# ECsimple.net
KiCad netlist of a schematic drawn in EAGLE
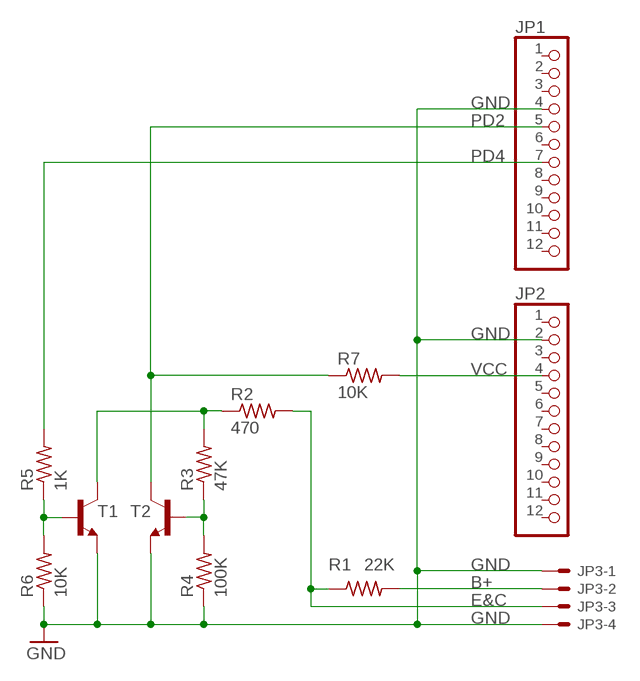
[diagram p0: schematic, sheet 1]

(export (version "E")
  (design (tool "Eeschema 10.0.6"))
  (components
    (comp (ref "JP1")
      (value "PINHD-1X12-CB")
      (footprint "eagle-import:1X12-CB")
      (libsource (lib "eagle-import") (part "PINHD-1X12-CB"))
    )
    (comp (ref "JP2")
      (value "PINHD-1X12-CB")
      (footprint "eagle-import:1X12-CB")
      (libsource (lib "eagle-import") (part "PINHD-1X12-CB"))
    )
    (comp (ref "JP3")
      (value "HDR_PLAIN_1X4")
      (footprint "eagle-import:HDR_1X4")
      (libsource (lib "eagle-import") (part "HDR_PLAIN_1X4"))
    )
    (comp (ref "R1")
      (value "22K")
      (footprint "eagle-import:0204_7")
      (libsource (lib "eagle-import") (part "R-US_0204/7"))
    )
    (comp (ref "R2")
      (value "470")
      (footprint "eagle-import:0204_7")
      (libsource (lib "eagle-import") (part "R-US_0204/7"))
    )
    (comp (ref "R3")
      (value "47K")
      (footprint "eagle-import:0204_7")
      (libsource (lib "eagle-import") (part "R-US_0204/7"))
    )
    (comp (ref "R4")
      (value "100K")
      (footprint "eagle-import:0204_7")
      (libsource (lib "eagle-import") (part "R-US_0204/7"))
    )
    (comp (ref "R5")
      (value "1K")
      (footprint "eagle-import:0204_7")
      (libsource (lib "eagle-import") (part "R-US_0204/7"))
    )
    (comp (ref "R6")
      (value "10K")
      (footprint "eagle-import:0204_7")
      (libsource (lib "eagle-import") (part "R-US_0204/7"))
    )
    (comp (ref "R7")
      (value "10K")
      (footprint "eagle-import:0204_7")
      (libsource (lib "eagle-import") (part "R-US_0204/7"))
    )
    (comp (ref "T1")
      (value "NPN-TRANSISTORCLEAN")
      (footprint "eagle-import:TO92-NONPOLARIZED-CLEAN")
      (libsource (lib "eagle-import") (part "NPN-TRANSISTORCLEAN"))
    )
    (comp (ref "T2")
      (value "NPN-TRANSISTORCLEAN")
      (footprint "eagle-import:TO92-NONPOLARIZED-CLEAN")
      (libsource (lib "eagle-import") (part "NPN-TRANSISTORCLEAN"))
    )
  )
  (nets
    (net (code "1") (name "/B+") (class "Default")
      (node (ref "JP3") (pin "2") (pinfunction "S_2") (pintype "passive"))
      (node (ref "R1") (pin "2") (pinfunction "2_2") (pintype "passive"))
    )
    (net (code "2") (name "/E&C") (class "Default")
      (node (ref "JP3") (pin "3") (pinfunction "S_3") (pintype "passive"))
      (node (ref "R1") (pin "1") (pinfunction "1_1") (pintype "passive"))
      (node (ref "R2") (pin "2") (pinfunction "2_2") (pintype "passive"))
    )
    (net (code "3") (name "/PD2") (class "Default")
      (node (ref "JP1") (pin "5") (pinfunction "5_5") (pintype "passive"))
      (node (ref "R7") (pin "1") (pinfunction "1_1") (pintype "passive"))
      (node (ref "T2") (pin "C") (pinfunction "C_C") (pintype "passive"))
    )
    (net (code "4") (name "/PD4") (class "Default")
      (node (ref "JP1") (pin "7") (pinfunction "7_7") (pintype "passive"))
      (node (ref "R5") (pin "2") (pinfunction "2_2") (pintype "passive"))
    )
    (net (code "5") (name "/VCC") (class "Default")
      (node (ref "JP2") (pin "4") (pinfunction "4_4") (pintype "passive"))
      (node (ref "R7") (pin "2") (pinfunction "2_2") (pintype "passive"))
    )
    (net (code "6") (name "GND") (class "Default")
      (node (ref "JP1") (pin "4") (pinfunction "4_4") (pintype "passive"))
      (node (ref "JP2") (pin "2") (pinfunction "2_2") (pintype "passive"))
      (node (ref "JP3") (pin "1") (pinfunction "S_1") (pintype "passive"))
      (node (ref "JP3") (pin "4") (pinfunction "S_4") (pintype "passive"))
      (node (ref "R4") (pin "1") (pinfunction "1_1") (pintype "passive"))
      (node (ref "R6") (pin "1") (pinfunction "1_1") (pintype "passive"))
      (node (ref "T1") (pin "E") (pinfunction "E_E") (pintype "passive"))
      (node (ref "T2") (pin "E") (pinfunction "E_E") (pintype "passive"))
    )
    (net (code "7") (name "Net-(R2-Pad1)") (class "Default")
      (node (ref "R2") (pin "1") (pinfunction "1_1") (pintype "passive"))
      (node (ref "R3") (pin "2") (pinfunction "2_2") (pintype "passive"))
      (node (ref "T1") (pin "C") (pinfunction "C_C") (pintype "passive"))
    )
    (net (code "8") (name "Net-(R3-Pad1)") (class "Default")
      (node (ref "R3") (pin "1") (pinfunction "1_1") (pintype "passive"))
      (node (ref "R4") (pin "2") (pinfunction "2_2") (pintype "passive"))
      (node (ref "T2") (pin "B") (pinfunction "B_B") (pintype "passive"))
    )
    (net (code "9") (name "Net-(R5-Pad1)") (class "Default")
      (node (ref "R5") (pin "1") (pinfunction "1_1") (pintype "passive"))
      (node (ref "R6") (pin "2") (pinfunction "2_2") (pintype "passive"))
      (node (ref "T1") (pin "B") (pinfunction "B_B") (pintype "passive"))
    )
    (net (code "10") (name "unconnected-(JP1-Pad1)") (class "Default")
      (node (ref "JP1") (pin "1") (pinfunction "1_1") (pintype "passive"))
    )
    (net (code "11") (name "unconnected-(JP1-Pad2)") (class "Default")
      (node (ref "JP1") (pin "2") (pinfunction "2_2") (pintype "passive"))
    )
    (net (code "12") (name "unconnected-(JP1-Pad3)") (class "Default")
      (node (ref "JP1") (pin "3") (pinfunction "3_3") (pintype "passive"))
    )
    (net (code "13") (name "unconnected-(JP1-Pad6)") (class "Default")
      (node (ref "JP1") (pin "6") (pinfunction "6_6") (pintype "passive"))
    )
    (net (code "14") (name "unconnected-(JP1-Pad8)") (class "Default")
      (node (ref "JP1") (pin "8") (pinfunction "8_8") (pintype "passive"))
    )
    (net (code "15") (name "unconnected-(JP1-Pad9)") (class "Default")
      (node (ref "JP1") (pin "9") (pinfunction "9_9") (pintype "passive"))
    )
    (net (code "16") (name "unconnected-(JP1-Pad10)") (class "Default")
      (node (ref "JP1") (pin "10") (pinfunction "10_10") (pintype "passive"))
    )
    (net (code "17") (name "unconnected-(JP1-Pad11)") (class "Default")
      (node (ref "JP1") (pin "11") (pinfunction "11_11") (pintype "passive"))
    )
    (net (code "18") (name "unconnected-(JP1-Pad12)") (class "Default")
      (node (ref "JP1") (pin "12") (pinfunction "12_12") (pintype "passive"))
    )
    (net (code "19") (name "unconnected-(JP2-Pad1)") (class "Default")
      (node (ref "JP2") (pin "1") (pinfunction "1_1") (pintype "passive"))
    )
    (net (code "20") (name "unconnected-(JP2-Pad3)") (class "Default")
      (node (ref "JP2") (pin "3") (pinfunction "3_3") (pintype "passive"))
    )
    (net (code "21") (name "unconnected-(JP2-Pad5)") (class "Default")
      (node (ref "JP2") (pin "5") (pinfunction "5_5") (pintype "passive"))
    )
    (net (code "22") (name "unconnected-(JP2-Pad6)") (class "Default")
      (node (ref "JP2") (pin "6") (pinfunction "6_6") (pintype "passive"))
    )
    (net (code "23") (name "unconnected-(JP2-Pad7)") (class "Default")
      (node (ref "JP2") (pin "7") (pinfunction "7_7") (pintype "passive"))
    )
    (net (code "24") (name "unconnected-(JP2-Pad8)") (class "Default")
      (node (ref "JP2") (pin "8") (pinfunction "8_8") (pintype "passive"))
    )
    (net (code "25") (name "unconnected-(JP2-Pad9)") (class "Default")
      (node (ref "JP2") (pin "9") (pinfunction "9_9") (pintype "passive"))
    )
    (net (code "26") (name "unconnected-(JP2-Pad10)") (class "Default")
      (node (ref "JP2") (pin "10") (pinfunction "10_10") (pintype "passive"))
    )
    (net (code "27") (name "unconnected-(JP2-Pad11)") (class "Default")
      (node (ref "JP2") (pin "11") (pinfunction "11_11") (pintype "passive"))
    )
    (net (code "28") (name "unconnected-(JP2-Pad12)") (class "Default")
      (node (ref "JP2") (pin "12") (pinfunction "12_12") (pintype "passive"))
    )
  )
)
